# Misc.net
KiCad netlist of a schematic drawn in Altium Designer
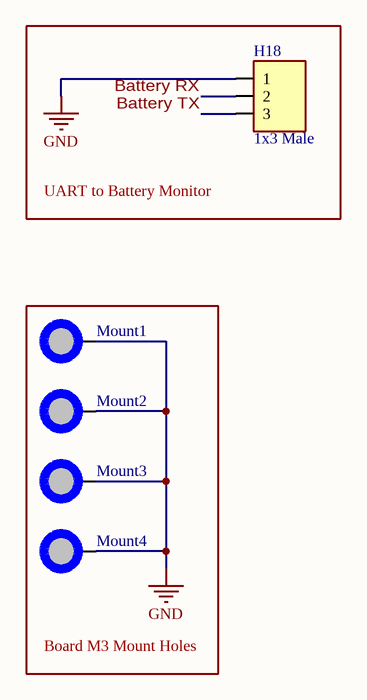
[diagram p0: Misc.SchDoc]

(export (version "E")
  (design (tool "Eeschema 10.0.6"))
  (components
    (comp (ref "H18")
      (value "1x3 Male")
      (footprint "[Header] Shrouded 1x3 Male")
      (description "070543-0037\r\nMates with 005057-9403")
      (libsource (lib "RADM Connectors") (part "[Header] Shrouded 1x3 Male"))
    )
    (comp (ref "Mount1")
      (value "M3 Mount Hole")
      (footprint "[Mount] M3 Mount Hole")
      (description "Place at least 4.5mm from board edge. Plated.")
      (libsource (lib "RADM Connectors") (part "[Mount] M3 Mount Hole"))
    )
    (comp (ref "Mount2")
      (value "M3 Mount Hole")
      (footprint "[Mount] M3 Mount Hole")
      (description "Place at least 4.5mm from board edge. Plated.")
      (libsource (lib "RADM Connectors") (part "[Mount] M3 Mount Hole"))
    )
    (comp (ref "Mount3")
      (value "M3 Mount Hole")
      (footprint "[Mount] M3 Mount Hole")
      (description "Place at least 4.5mm from board edge. Plated.")
      (libsource (lib "RADM Connectors") (part "[Mount] M3 Mount Hole"))
    )
    (comp (ref "Mount4")
      (value "M3 Mount Hole")
      (footprint "[Mount] M3 Mount Hole")
      (description "Place at least 4.5mm from board edge. Plated.")
      (libsource (lib "RADM Connectors") (part "[Mount] M3 Mount Hole"))
    )
  )
  (nets
    (net (code "1") (name "/Battery RX") (class "Default")
      (node (ref "H18") (pin "2") (pinfunction "2_2") (pintype "passive"))
    )
    (net (code "2") (name "/Battery TX") (class "Default")
      (node (ref "H18") (pin "3") (pinfunction "3_3") (pintype "passive"))
    )
    (net (code "3") (name "GND") (class "Default")
      (node (ref "H18") (pin "1") (pinfunction "1_1") (pintype "passive"))
      (node (ref "Mount1") (pin "1") (pintype "power_in"))
      (node (ref "Mount2") (pin "1") (pintype "power_in"))
      (node (ref "Mount3") (pin "1") (pintype "power_in"))
      (node (ref "Mount4") (pin "1") (pintype "power_in"))
    )
  )
)
